# design.net
KiCad netlist of a schematic drawn in EAGLE
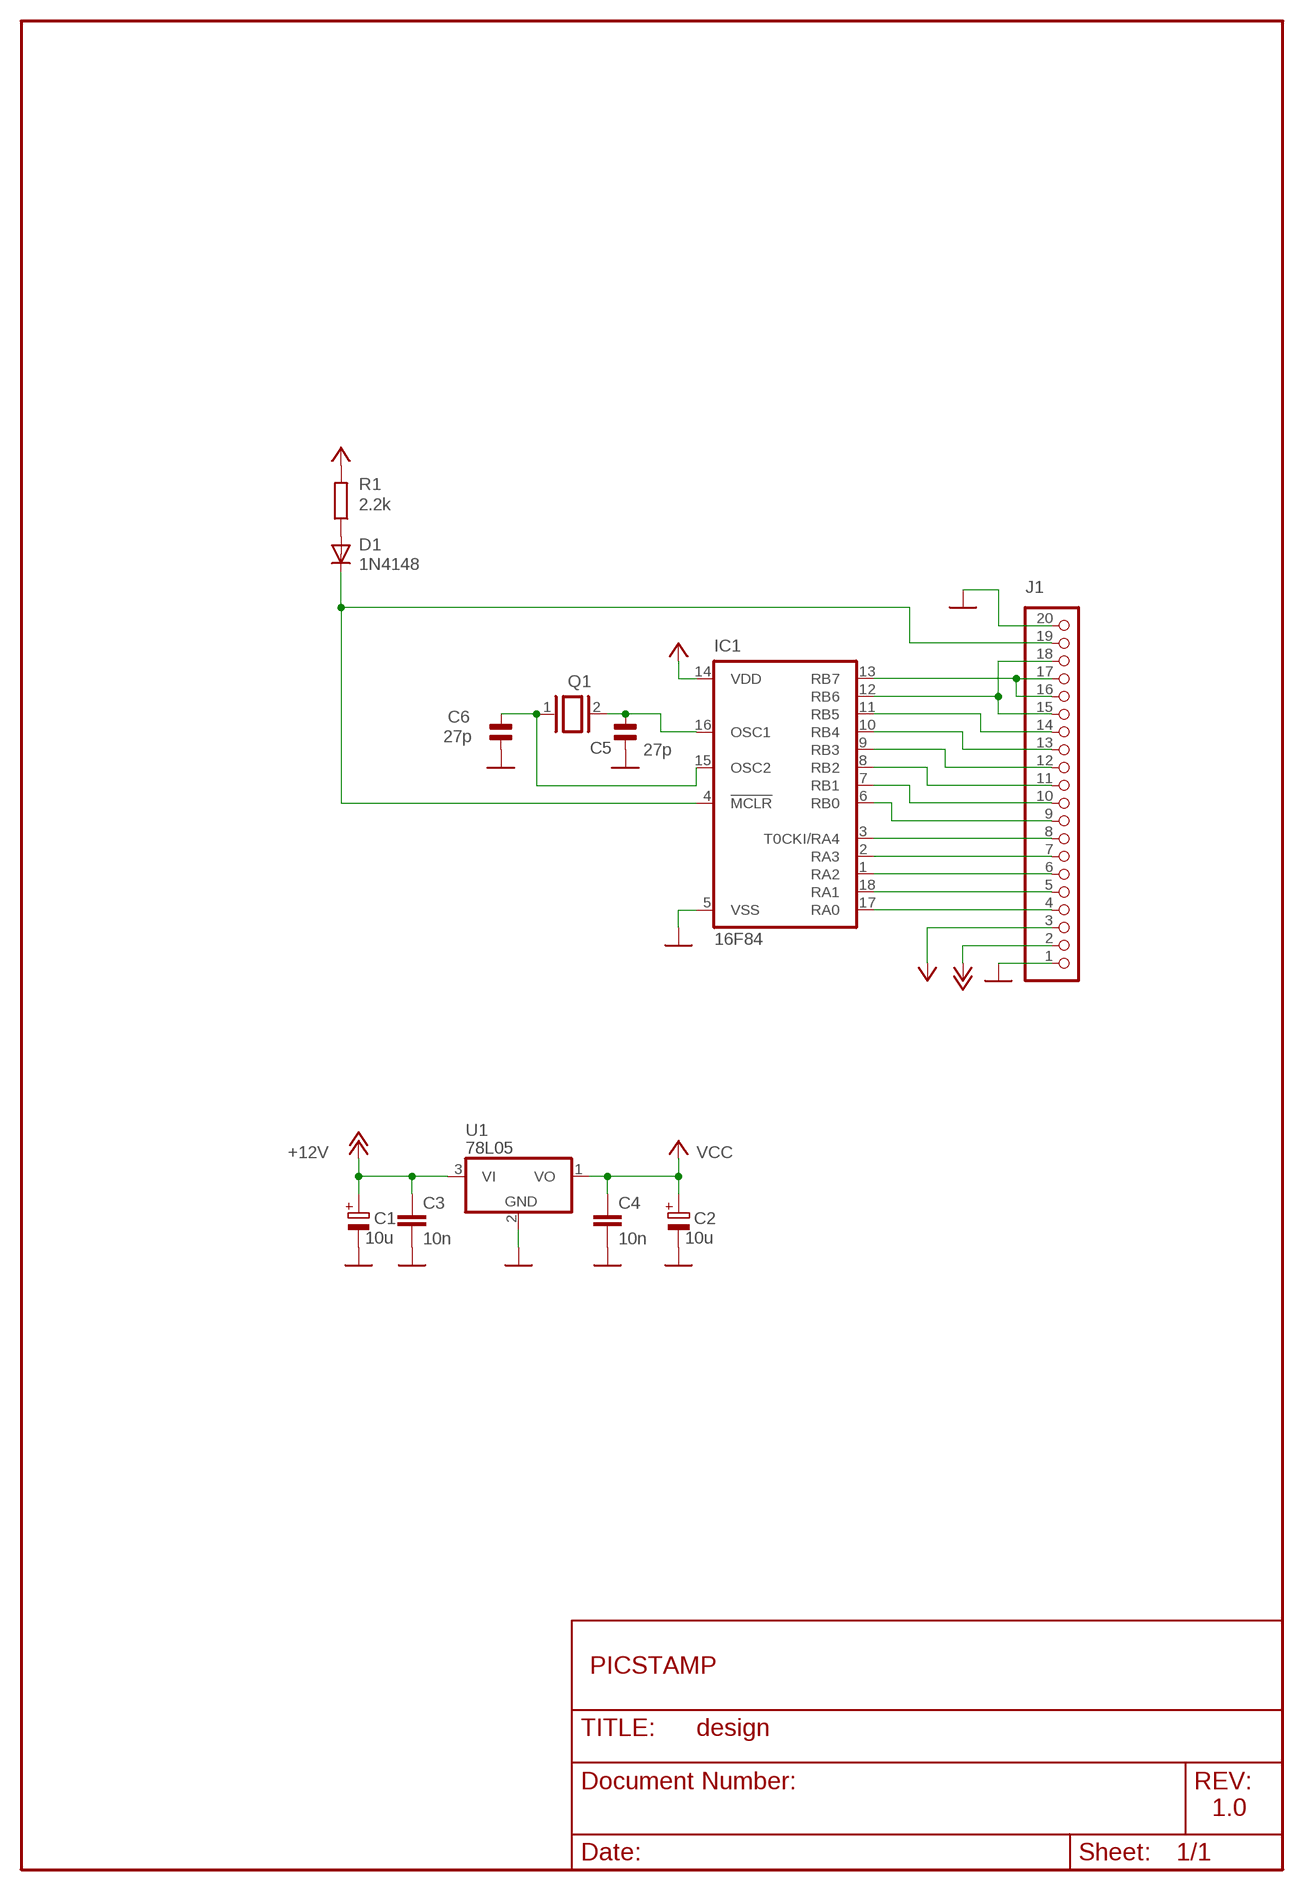
[diagram p0: schematic, sheet 1]

(export (version "E")
  (design (tool "Eeschema 10.0.6"))
  (components
    (comp (ref "C1")
      (value "10u")
      (footprint "eagle-import:E2,5-6")
      (fields (field (name "MPN") "CAP-10U-25V-ELEC"))
      (libsource (lib "eagle-import") (part "E2,5-6"))
    )
    (comp (ref "C2")
      (value "10u")
      (footprint "eagle-import:E2,5-6")
      (fields (field (name "MPN") "CAP-10U-25V-ELEC"))
      (libsource (lib "eagle-import") (part "E2,5-6"))
    )
    (comp (ref "C3")
      (value "10n")
      (footprint "eagle-import:C025-025X050")
      (fields (field (name "MPN") "CAP-10N-50V-X7R"))
      (libsource (lib "eagle-import") (part "C-EU025-025X050"))
    )
    (comp (ref "C4")
      (value "10n")
      (footprint "eagle-import:C025-025X050")
      (fields (field (name "MPN") "CAP-10N-50V-X7R"))
      (libsource (lib "eagle-import") (part "C-EU025-025X050"))
    )
    (comp (ref "C5")
      (value "27p")
      (footprint "eagle-import:C2,5-2")
      (fields (field (name "MPN") "CAP-27P-50V-C0G"))
      (libsource (lib "eagle-import") (part "C2.5/2"))
    )
    (comp (ref "C6")
      (value "27p")
      (footprint "eagle-import:C2,5-2")
      (fields (field (name "DNP") "yes") (field (name "MPN") "CAP-27P-50V-C0G"))
      (libsource (lib "eagle-import") (part "C2.5/2"))
    )
    (comp (ref "D1")
      (value "1N4148")
      (footprint "eagle-import:DO35-10")
      (fields (field (name "MPN") "1N4148W-TP"))
      (libsource (lib "eagle-import") (part "1N4148?"))
    )
    (comp (ref "IC1")
      (value "16F84")
      (footprint "eagle-import:DIL18")
      (fields (field (name "MPN") "PIC16F84A-04/P"))
      (libsource (lib "eagle-import") (part "PIC16F8P4A"))
    )
    (comp (ref "J1")
      (value "PINHD-1X20")
      (footprint "eagle-import:1X20")
      (fields (field (name "MPN") "CONN-PINHD-1X20"))
      (libsource (lib "eagle-import") (part "PINHD-1X20"))
    )
    (comp (ref "Q1")
      (value "XTAL/S")
      (footprint "eagle-import:QS")
      (fields (field (name "DNP") "yes") (field (name "MPN") "XTAL-4MHZ"))
      (libsource (lib "eagle-import") (part "XTAL/S"))
    )
    (comp (ref "R1")
      (value "2.2k")
      (footprint "eagle-import:0207_10")
      (fields (field (name "MPN") "RES-2K2-0207"))
      (libsource (lib "eagle-import") (part "R-EU_0207/10"))
    )
    (comp (ref "U1")
      (value "78L05")
      (footprint "eagle-import:TO92")
      (fields (field (name "MPN") "78L05-ACZ"))
      (libsource (lib "eagle-import") (part "78LXXZ"))
    )
  )
  (nets
    (net (code "1") (name "+12V") (class "Default")
      (node (ref "C1") (pin "+") (pinfunction "+_+") (pintype "passive"))
      (node (ref "C3") (pin "2") (pinfunction "2_2") (pintype "passive"))
      (node (ref "J1") (pin "2") (pinfunction "2_2") (pintype "passive"))
      (node (ref "U1") (pin "3") (pinfunction "VI_3") (pintype "input"))
    )
    (net (code "2") (name "GND") (class "Default")
      (node (ref "C1") (pin "-") (pinfunction "-_-") (pintype "passive"))
      (node (ref "C2") (pin "-") (pinfunction "-_-") (pintype "passive"))
      (node (ref "C3") (pin "1") (pinfunction "1_1") (pintype "passive"))
      (node (ref "C4") (pin "1") (pinfunction "1_1") (pintype "passive"))
      (node (ref "C5") (pin "1") (pinfunction "1_1") (pintype "passive"))
      (node (ref "C6") (pin "1") (pinfunction "1_1") (pintype "passive"))
      (node (ref "IC1") (pin "5") (pinfunction "VSS_5") (pintype "power_in"))
      (node (ref "J1") (pin "1") (pinfunction "1_1") (pintype "passive"))
      (node (ref "J1") (pin "20") (pinfunction "20_20") (pintype "passive"))
      (node (ref "U1") (pin "2") (pinfunction "GND_2") (pintype "passive"))
    )
    (net (code "3") (name "Net-(D1-C)") (class "Default")
      (node (ref "D1") (pin "K") (pinfunction "C_K") (pintype "passive"))
      (node (ref "IC1") (pin "4") (pinfunction "~{MCLR}_4") (pintype "input"))
      (node (ref "J1") (pin "19") (pinfunction "19_19") (pintype "passive"))
    )
    (net (code "4") (name "Net-(D1-PadA)") (class "Default")
      (node (ref "D1") (pin "A") (pinfunction "A_A") (pintype "passive"))
      (node (ref "R1") (pin "1") (pinfunction "1_1") (pintype "passive"))
    )
    (net (code "5") (name "Net-(IC1-OSC1)") (class "Default")
      (node (ref "C5") (pin "2") (pinfunction "2_2") (pintype "passive"))
      (node (ref "IC1") (pin "16") (pinfunction "OSC1_16") (pintype "input"))
      (node (ref "Q1") (pin "2") (pinfunction "2_2") (pintype "passive"))
    )
    (net (code "6") (name "Net-(IC1-OSC2)") (class "Default")
      (node (ref "C6") (pin "2") (pinfunction "2_2") (pintype "passive"))
      (node (ref "IC1") (pin "15") (pinfunction "OSC2_15") (pintype "output"))
      (node (ref "Q1") (pin "1") (pinfunction "1_1") (pintype "passive"))
    )
    (net (code "7") (name "Net-(IC1-RA0)") (class "Default")
      (node (ref "IC1") (pin "17") (pinfunction "RA0_17") (pintype "bidirectional"))
      (node (ref "J1") (pin "4") (pinfunction "4_4") (pintype "passive"))
    )
    (net (code "8") (name "Net-(IC1-RA1)") (class "Default")
      (node (ref "IC1") (pin "18") (pinfunction "RA1_18") (pintype "bidirectional"))
      (node (ref "J1") (pin "5") (pinfunction "5_5") (pintype "passive"))
    )
    (net (code "9") (name "Net-(IC1-RA2)") (class "Default")
      (node (ref "IC1") (pin "1") (pinfunction "RA2_1") (pintype "bidirectional"))
      (node (ref "J1") (pin "6") (pinfunction "6_6") (pintype "passive"))
    )
    (net (code "10") (name "Net-(IC1-RA3)") (class "Default")
      (node (ref "IC1") (pin "2") (pinfunction "RA3_2") (pintype "bidirectional"))
      (node (ref "J1") (pin "7") (pinfunction "7_7") (pintype "passive"))
    )
    (net (code "11") (name "Net-(IC1-RB0)") (class "Default")
      (node (ref "IC1") (pin "6") (pinfunction "RB0_6") (pintype "bidirectional"))
      (node (ref "J1") (pin "9") (pinfunction "9_9") (pintype "passive"))
    )
    (net (code "12") (name "Net-(IC1-RB1)") (class "Default")
      (node (ref "IC1") (pin "7") (pinfunction "RB1_7") (pintype "bidirectional"))
      (node (ref "J1") (pin "10") (pinfunction "10_10") (pintype "passive"))
    )
    (net (code "13") (name "Net-(IC1-RB2)") (class "Default")
      (node (ref "IC1") (pin "8") (pinfunction "RB2_8") (pintype "bidirectional"))
      (node (ref "J1") (pin "11") (pinfunction "11_11") (pintype "passive"))
    )
    (net (code "14") (name "Net-(IC1-RB3)") (class "Default")
      (node (ref "IC1") (pin "9") (pinfunction "RB3_9") (pintype "bidirectional"))
      (node (ref "J1") (pin "12") (pinfunction "12_12") (pintype "passive"))
    )
    (net (code "15") (name "Net-(IC1-RB4)") (class "Default")
      (node (ref "IC1") (pin "10") (pinfunction "RB4_10") (pintype "bidirectional"))
      (node (ref "J1") (pin "13") (pinfunction "13_13") (pintype "passive"))
    )
    (net (code "16") (name "Net-(IC1-RB5)") (class "Default")
      (node (ref "IC1") (pin "11") (pinfunction "RB5_11") (pintype "bidirectional"))
      (node (ref "J1") (pin "14") (pinfunction "14_14") (pintype "passive"))
    )
    (net (code "17") (name "Net-(IC1-RB6)") (class "Default")
      (node (ref "IC1") (pin "12") (pinfunction "RB6_12") (pintype "bidirectional"))
      (node (ref "J1") (pin "15") (pinfunction "15_15") (pintype "passive"))
      (node (ref "J1") (pin "18") (pinfunction "18_18") (pintype "passive"))
    )
    (net (code "18") (name "Net-(IC1-RB7)") (class "Default")
      (node (ref "IC1") (pin "13") (pinfunction "RB7_13") (pintype "bidirectional"))
      (node (ref "J1") (pin "16") (pinfunction "16_16") (pintype "passive"))
      (node (ref "J1") (pin "17") (pinfunction "17_17") (pintype "passive"))
    )
    (net (code "19") (name "Net-(IC1-T0CKI{slash}RA4)") (class "Default")
      (node (ref "IC1") (pin "3") (pinfunction "T0CKI/RA4_3") (pintype "bidirectional"))
      (node (ref "J1") (pin "8") (pinfunction "8_8") (pintype "passive"))
    )
    (net (code "20") (name "VCC") (class "Default")
      (node (ref "C2") (pin "+") (pinfunction "+_+") (pintype "passive"))
      (node (ref "C4") (pin "2") (pinfunction "2_2") (pintype "passive"))
      (node (ref "IC1") (pin "14") (pinfunction "VDD_14") (pintype "power_in"))
      (node (ref "J1") (pin "3") (pinfunction "3_3") (pintype "passive"))
      (node (ref "R1") (pin "2") (pinfunction "2_2") (pintype "passive"))
      (node (ref "U1") (pin "1") (pinfunction "VO_1") (pintype "output"))
    )
  )
)
